# Eyecillator.net
KiCad netlist of a schematic drawn in EAGLE
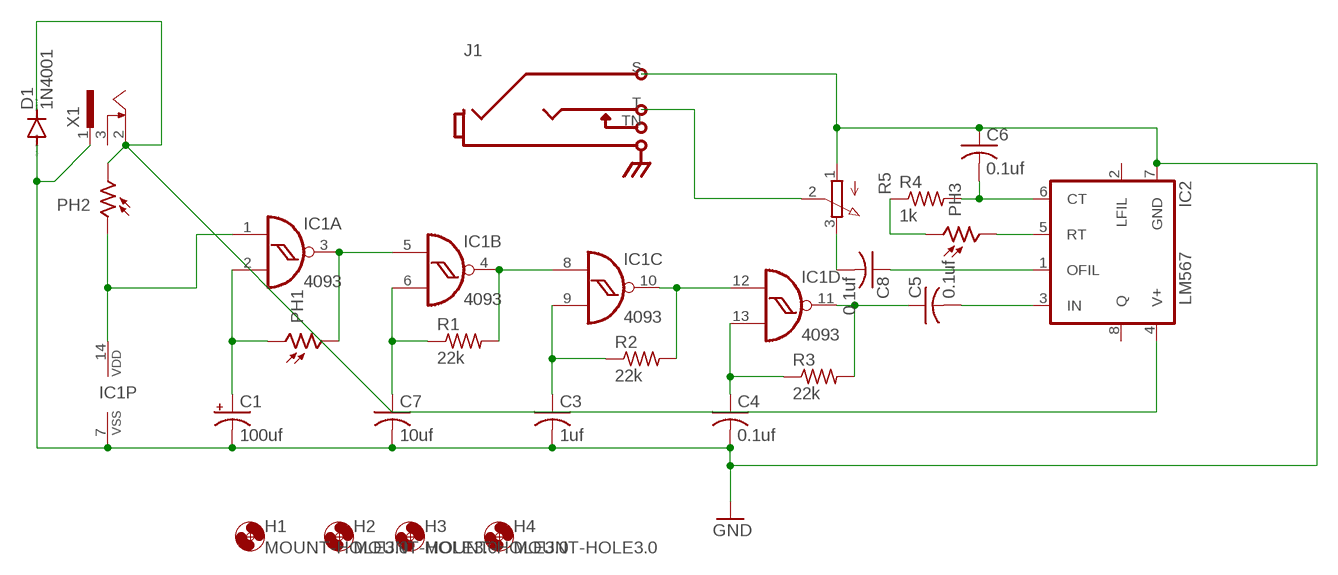
[diagram p0: schematic, sheet 1]

(export (version "E")
  (design (tool "Eeschema 10.0.6"))
  (components
    (comp (ref "C1")
      (value "100uf")
      (footprint "eagle-import:E2,5-6E")
      (libsource (lib "eagle-import") (part "CPOL-USE2,5-6E"))
    )
    (comp (ref "C3")
      (value "1uf")
      (footprint "eagle-import:C050-025X075")
      (libsource (lib "eagle-import") (part "C-US050-025X075"))
    )
    (comp (ref "C4")
      (value "0.1uf")
      (footprint "eagle-import:C050-025X075")
      (libsource (lib "eagle-import") (part "C-US050-025X075"))
    )
    (comp (ref "C5")
      (value "0.1uf")
      (footprint "eagle-import:C050-025X075")
      (libsource (lib "eagle-import") (part "C-US050-025X075"))
    )
    (comp (ref "C6")
      (value "0.1uf")
      (footprint "eagle-import:C050-025X075")
      (libsource (lib "eagle-import") (part "C-US050-025X075"))
    )
    (comp (ref "C7")
      (value "10uf")
      (footprint "eagle-import:C050-025X075")
      (libsource (lib "eagle-import") (part "C-US050-025X075"))
    )
    (comp (ref "C8")
      (value "0.1uf")
      (footprint "eagle-import:C050-025X075")
      (libsource (lib "eagle-import") (part "C-US050-025X075"))
    )
    (comp (ref "D1")
      (value "1N4001")
      (footprint "eagle-import:DO41-10")
      (libsource (lib "eagle-import") (part "1N4004"))
    )
    (comp (ref "H1")
      (value "MOUNT-HOLE3.0")
      (footprint "eagle-import:3,0")
      (libsource (lib "eagle-import") (part "MOUNT-HOLE3.0"))
    )
    (comp (ref "H2")
      (value "MOUNT-HOLE3.0")
      (footprint "eagle-import:3,0")
      (libsource (lib "eagle-import") (part "MOUNT-HOLE3.0"))
    )
    (comp (ref "H3")
      (value "MOUNT-HOLE3.0")
      (footprint "eagle-import:3,0")
      (libsource (lib "eagle-import") (part "MOUNT-HOLE3.0"))
    )
    (comp (ref "H4")
      (value "MOUNT-HOLE3.0")
      (footprint "eagle-import:3,0")
      (libsource (lib "eagle-import") (part "MOUNT-HOLE3.0"))
    )
    (comp (ref "IC1")
      (value "4093")
      (footprint "eagle-import:DIL14")
      (libsource (lib "eagle-import") (part "4093N"))
    )
    (comp (ref "IC2")
      (value "LM567")
      (footprint "eagle-import:DIL08")
      (libsource (lib "eagle-import") (part "567NLM"))
    )
    (comp (ref "J1")
      (value "MONOSW1GND")
      (footprint "eagle-import:NEUTRIK-NRJ4HM-1")
      (libsource (lib "eagle-import") (part "MONOSW1GND"))
    )
    (comp (ref "PH1")
      (value "VT90N1")
      (footprint "eagle-import:VT900")
      (libsource (lib "eagle-import") (part "VT90N1"))
    )
    (comp (ref "PH2")
      (value "VT90N1")
      (footprint "eagle-import:VT900")
      (libsource (lib "eagle-import") (part "VT90N1"))
    )
    (comp (ref "PH3")
      (value "VT90N1")
      (footprint "eagle-import:VT900")
      (libsource (lib "eagle-import") (part "VT90N1"))
    )
    (comp (ref "R1")
      (value "22k")
      (footprint "eagle-import:0207_7")
      (libsource (lib "eagle-import") (part "R-US_0207/7"))
    )
    (comp (ref "R2")
      (value "22k")
      (footprint "eagle-import:0207_7")
      (libsource (lib "eagle-import") (part "R-US_0207/7"))
    )
    (comp (ref "R3")
      (value "22k")
      (footprint "eagle-import:0207_7")
      (libsource (lib "eagle-import") (part "R-US_0207/7"))
    )
    (comp (ref "R4")
      (value "1k")
      (footprint "eagle-import:0207_7")
      (libsource (lib "eagle-import") (part "R-US_0207/7"))
    )
    (comp (ref "R5")
      (value "EVUF2L")
      (footprint "eagle-import:EVUFXL")
      (libsource (lib "eagle-import") (part "EVULF2"))
    )
    (comp (ref "X1")
      (value "SCD-014A")
      (footprint "eagle-import:SCD-014-A")
      (libsource (lib "eagle-import") (part "SCD-014A"))
    )
  )
  (nets
    (net (code "1") (name "GND") (class "Default")
      (node (ref "C1") (pin "-") (pinfunction "-_-") (pintype "passive"))
      (node (ref "C3") (pin "2") (pinfunction "2_2") (pintype "passive"))
      (node (ref "C4") (pin "2") (pinfunction "2_2") (pintype "passive"))
      (node (ref "C6") (pin "1") (pinfunction "1_1") (pintype "passive"))
      (node (ref "C7") (pin "2") (pinfunction "2_2") (pintype "passive"))
      (node (ref "D1") (pin "A") (pinfunction "A_A") (pintype "passive"))
      (node (ref "IC1") (pin "7") (pinfunction "VSS_7") (pintype "power_in"))
      (node (ref "IC2") (pin "7") (pinfunction "GND_7") (pintype "power_in"))
      (node (ref "J1") (pin "S") (pinfunction "S_S") (pintype "passive"))
      (node (ref "R5") (pin "1") (pinfunction "A_1") (pintype "passive"))
      (node (ref "X1") (pin "1") (pinfunction "1_1") (pintype "passive"))
    )
    (net (code "2") (name "Net-(IC1A-I0)") (class "Default")
      (node (ref "IC1") (pin "1") (pinfunction "I0_1") (pintype "input"))
      (node (ref "IC1") (pin "14") (pinfunction "VDD_14") (pintype "power_in"))
      (node (ref "PH2") (pin "1") (pinfunction "1_1") (pintype "passive"))
    )
    (net (code "3") (name "Net-(IC1A-I1)") (class "Default")
      (node (ref "C1") (pin "+") (pinfunction "+_+") (pintype "passive"))
      (node (ref "IC1") (pin "2") (pinfunction "I1_2") (pintype "input"))
      (node (ref "PH1") (pin "1") (pinfunction "1_1") (pintype "passive"))
    )
    (net (code "4") (name "Net-(IC1A-O)") (class "Default")
      (node (ref "IC1") (pin "3") (pinfunction "O_3") (pintype "output"))
      (node (ref "IC1") (pin "5") (pinfunction "I0_5") (pintype "input"))
      (node (ref "PH1") (pin "2") (pinfunction "2_2") (pintype "passive"))
    )
    (net (code "5") (name "Net-(IC1B-I1)") (class "Default")
      (node (ref "C7") (pin "1") (pinfunction "1_1") (pintype "passive"))
      (node (ref "IC1") (pin "6") (pinfunction "I1_6") (pintype "input"))
      (node (ref "R1") (pin "1") (pinfunction "1_1") (pintype "passive"))
    )
    (net (code "6") (name "Net-(IC1B-O)") (class "Default")
      (node (ref "IC1") (pin "4") (pinfunction "O_4") (pintype "output"))
      (node (ref "IC1") (pin "8") (pinfunction "I0_8") (pintype "input"))
      (node (ref "R1") (pin "2") (pinfunction "2_2") (pintype "passive"))
    )
    (net (code "7") (name "Net-(IC1C-I1)") (class "Default")
      (node (ref "C3") (pin "1") (pinfunction "1_1") (pintype "passive"))
      (node (ref "IC1") (pin "9") (pinfunction "I1_9") (pintype "input"))
      (node (ref "R2") (pin "1") (pinfunction "1_1") (pintype "passive"))
    )
    (net (code "8") (name "Net-(IC1C-O)") (class "Default")
      (node (ref "IC1") (pin "10") (pinfunction "O_10") (pintype "output"))
      (node (ref "IC1") (pin "12") (pinfunction "I0_12") (pintype "input"))
      (node (ref "R2") (pin "2") (pinfunction "2_2") (pintype "passive"))
    )
    (net (code "9") (name "Net-(IC1D-I1)") (class "Default")
      (node (ref "C4") (pin "1") (pinfunction "1_1") (pintype "passive"))
      (node (ref "IC1") (pin "13") (pinfunction "I1_13") (pintype "input"))
      (node (ref "R3") (pin "1") (pinfunction "1_1") (pintype "passive"))
    )
    (net (code "10") (name "Net-(IC1D-O)") (class "Default")
      (node (ref "C5") (pin "1") (pinfunction "1_1") (pintype "passive"))
      (node (ref "IC1") (pin "11") (pinfunction "O_11") (pintype "output"))
      (node (ref "R3") (pin "2") (pinfunction "2_2") (pintype "passive"))
    )
    (net (code "11") (name "Net-(IC2-CT)") (class "Default")
      (node (ref "C6") (pin "2") (pinfunction "2_2") (pintype "passive"))
      (node (ref "IC2") (pin "6") (pinfunction "CT_6") (pintype "passive"))
      (node (ref "R4") (pin "2") (pinfunction "2_2") (pintype "passive"))
    )
    (net (code "12") (name "Net-(IC2-IN)") (class "Default")
      (node (ref "C5") (pin "2") (pinfunction "2_2") (pintype "passive"))
      (node (ref "IC2") (pin "3") (pinfunction "IN_3") (pintype "input"))
    )
    (net (code "13") (name "Net-(IC2-OFIL)") (class "Default")
      (node (ref "C8") (pin "1") (pinfunction "1_1") (pintype "passive"))
      (node (ref "IC2") (pin "1") (pinfunction "OFIL_1") (pintype "output"))
    )
    (net (code "14") (name "Net-(IC2-RT)") (class "Default")
      (node (ref "IC2") (pin "5") (pinfunction "RT_5") (pintype "passive"))
      (node (ref "PH3") (pin "2") (pinfunction "2_2") (pintype "passive"))
    )
    (net (code "15") (name "Net-(IC2-V+)") (class "Default")
      (node (ref "D1") (pin "C") (pinfunction "C_C") (pintype "passive"))
      (node (ref "IC2") (pin "4") (pinfunction "V+_4") (pintype "power_in"))
      (node (ref "PH2") (pin "2") (pinfunction "2_2") (pintype "passive"))
      (node (ref "X1") (pin "2") (pinfunction "2_2") (pintype "passive"))
    )
    (net (code "16") (name "Net-(PH3-Pad1)") (class "Default")
      (node (ref "PH3") (pin "1") (pinfunction "1_1") (pintype "passive"))
      (node (ref "R4") (pin "1") (pinfunction "1_1") (pintype "passive"))
    )
    (net (code "17") (name "Net-(R5-E)") (class "Default")
      (node (ref "C8") (pin "2") (pinfunction "2_2") (pintype "passive"))
      (node (ref "R5") (pin "3") (pinfunction "E_3") (pintype "passive"))
    )
    (net (code "18") (name "Net-(R5-S)") (class "Default")
      (node (ref "J1") (pin "T") (pinfunction "T_T") (pintype "passive"))
      (node (ref "R5") (pin "2") (pinfunction "S_2") (pintype "passive"))
    )
    (net (code "19") (name "unconnected-(IC2-LFIL-Pad2)") (class "Default")
      (node (ref "IC2") (pin "2") (pinfunction "LFIL_2") (pintype "passive"))
    )
    (net (code "20") (name "unconnected-(IC2-Q-Pad8)") (class "Default")
      (node (ref "IC2") (pin "8") (pinfunction "Q_8") (pintype "output"))
    )
    (net (code "21") (name "unconnected-(J1-PadTN)") (class "Default")
      (node (ref "J1") (pin "TN") (pinfunction "TN_TN") (pintype "passive"))
    )
    (net (code "22") (name "unconnected-(X1-Pad3)") (class "Default")
      (node (ref "X1") (pin "3") (pinfunction "3_3") (pintype "passive"))
    )
  )
)
